# analogSignals.net
KiCad netlist of a schematic drawn in Altium Designer
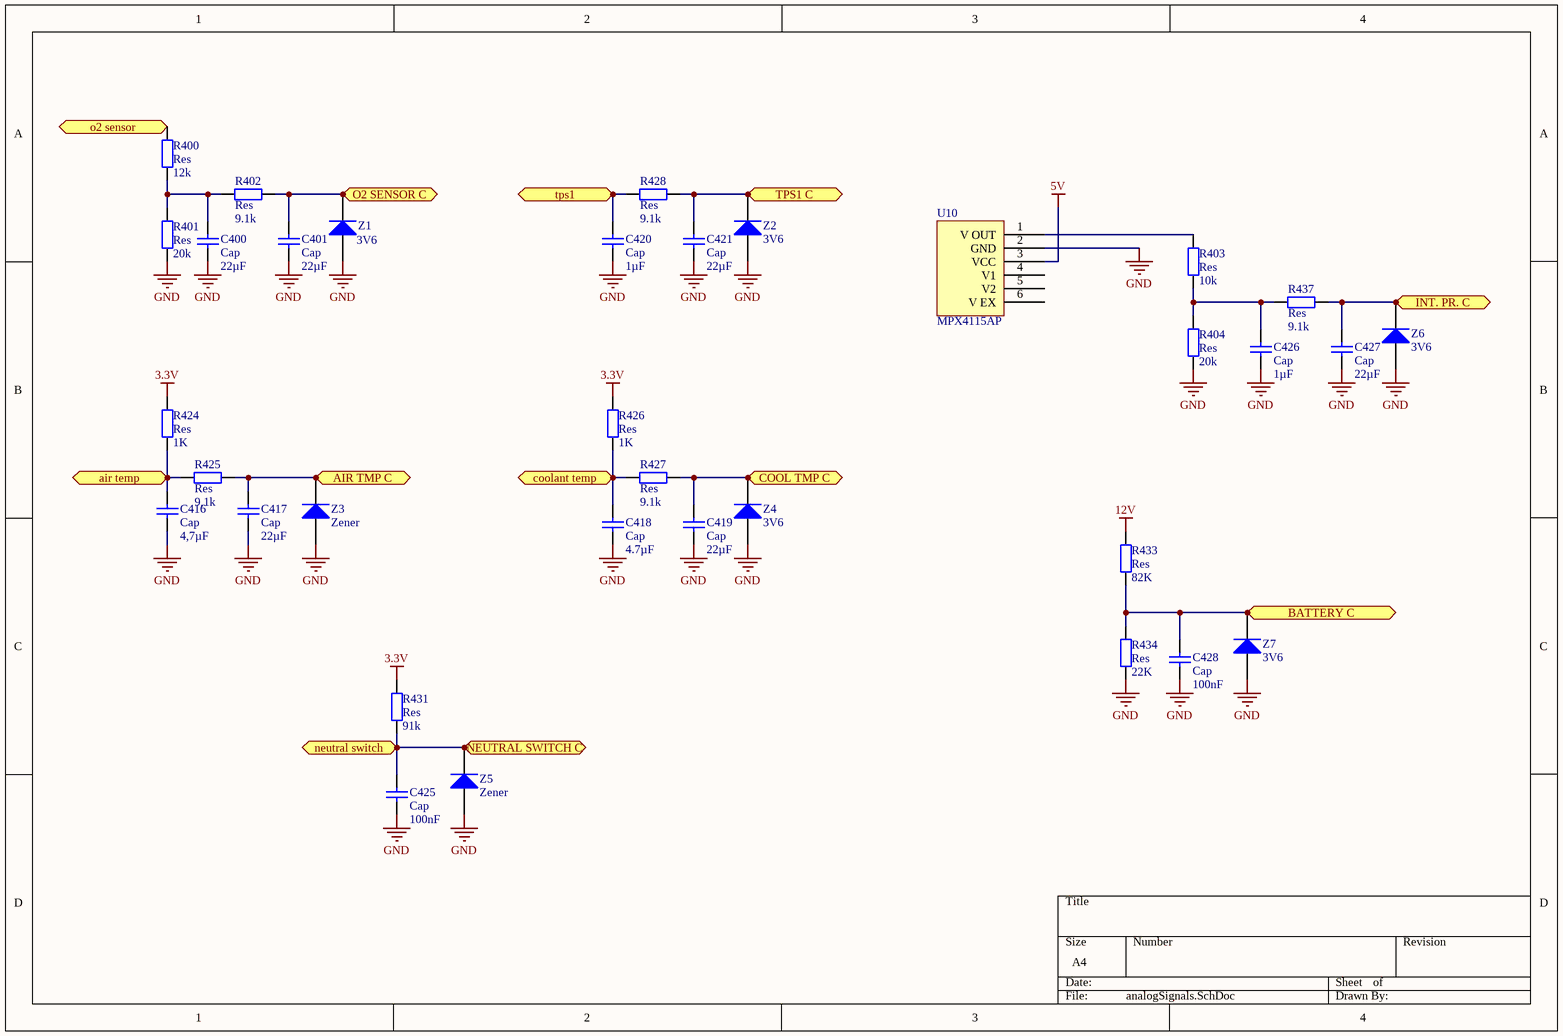
[diagram p0: analogSignals.SchDoc]

(export (version "E")
  (design (tool "Eeschema 10.0.6"))
  (components
    (comp (ref "C400")
      (value "Cap")
      (footprint "1206 footprint")
      (fields (field (name "ALTIUM_VALUE") "22µF"))
      (libsource (lib "ArduinoNano") (part "Cap"))
    )
    (comp (ref "C401")
      (value "Cap")
      (footprint "1206 footprint")
      (fields (field (name "ALTIUM_VALUE") "22µF"))
      (libsource (lib "ArduinoNano") (part "Cap"))
    )
    (comp (ref "C416")
      (value "Cap")
      (footprint "1206 footprint")
      (fields (field (name "ALTIUM_VALUE") "4,7µF"))
      (libsource (lib "ArduinoNano") (part "Cap"))
    )
    (comp (ref "C417")
      (value "Cap")
      (footprint "1206 footprint")
      (fields (field (name "ALTIUM_VALUE") "22µF"))
      (libsource (lib "ArduinoNano") (part "Cap"))
    )
    (comp (ref "C418")
      (value "Cap")
      (footprint "1206 footprint")
      (fields (field (name "ALTIUM_VALUE") "4.7µF"))
      (libsource (lib "ArduinoNano") (part "Cap"))
    )
    (comp (ref "C419")
      (value "Cap")
      (footprint "1206 footprint")
      (fields (field (name "ALTIUM_VALUE") "22µF"))
      (libsource (lib "ArduinoNano") (part "Cap"))
    )
    (comp (ref "C420")
      (value "Cap")
      (footprint "1206 footprint")
      (fields (field (name "ALTIUM_VALUE") "1µF"))
      (libsource (lib "ArduinoNano") (part "Cap"))
    )
    (comp (ref "C421")
      (value "Cap")
      (footprint "1206 footprint")
      (fields (field (name "ALTIUM_VALUE") "22µF"))
      (libsource (lib "ArduinoNano") (part "Cap"))
    )
    (comp (ref "C425")
      (value "Cap")
      (footprint "1206 footprint")
      (fields (field (name "ALTIUM_VALUE") "100nF"))
      (libsource (lib "ArduinoNano") (part "Cap"))
    )
    (comp (ref "C426")
      (value "Cap")
      (footprint "1206 footprint")
      (fields (field (name "ALTIUM_VALUE") "1µF"))
      (libsource (lib "ArduinoNano") (part "Cap"))
    )
    (comp (ref "C427")
      (value "Cap")
      (footprint "1206 footprint")
      (fields (field (name "ALTIUM_VALUE") "22µF"))
      (libsource (lib "ArduinoNano") (part "Cap"))
    )
    (comp (ref "C428")
      (value "Cap")
      (footprint "1206 footprint")
      (fields (field (name "ALTIUM_VALUE") "100nF"))
      (libsource (lib "ArduinoNano") (part "Cap"))
    )
    (comp (ref "R400")
      (value "Res")
      (footprint "1206 footprint")
      (fields (field (name "ALTIUM_VALUE") "12k"))
      (libsource (lib "ArduinoNano") (part "Res"))
    )
    (comp (ref "R401")
      (value "Res")
      (footprint "1206 footprint")
      (fields (field (name "ALTIUM_VALUE") "20k"))
      (libsource (lib "ArduinoNano") (part "Res"))
    )
    (comp (ref "R402")
      (value "Res")
      (footprint "1206 footprint")
      (fields (field (name "ALTIUM_VALUE") "9.1k"))
      (libsource (lib "") (part "Res_1"))
    )
    (comp (ref "R403")
      (value "Res")
      (footprint "1206 footprint")
      (fields (field (name "ALTIUM_VALUE") "10k"))
      (libsource (lib "ArduinoNano") (part "Res"))
    )
    (comp (ref "R404")
      (value "Res")
      (footprint "1206 footprint")
      (fields (field (name "ALTIUM_VALUE") "20k"))
      (libsource (lib "ArduinoNano") (part "Res"))
    )
    (comp (ref "R424")
      (value "Res")
      (footprint "1206 footprint")
      (fields (field (name "ALTIUM_VALUE") "1K"))
      (libsource (lib "ArduinoNano") (part "Res"))
    )
    (comp (ref "R425")
      (value "Res")
      (footprint "1206 footprint")
      (fields (field (name "ALTIUM_VALUE") "9,1k"))
      (libsource (lib "") (part "Res_1"))
    )
    (comp (ref "R426")
      (value "Res")
      (footprint "1206 footprint")
      (fields (field (name "ALTIUM_VALUE") "1K"))
      (libsource (lib "ArduinoNano") (part "Res"))
    )
    (comp (ref "R427")
      (value "Res")
      (footprint "1206 footprint")
      (fields (field (name "ALTIUM_VALUE") "9.1k"))
      (libsource (lib "") (part "Res_1"))
    )
    (comp (ref "R428")
      (value "Res")
      (footprint "1206 footprint")
      (fields (field (name "ALTIUM_VALUE") "9.1k"))
      (libsource (lib "") (part "Res_1"))
    )
    (comp (ref "R431")
      (value "Res")
      (footprint "1206 footprint")
      (fields (field (name "ALTIUM_VALUE") "91k"))
      (libsource (lib "ArduinoNano") (part "Res"))
    )
    (comp (ref "R433")
      (value "Res")
      (footprint "1206 footprint")
      (fields (field (name "ALTIUM_VALUE") "82K"))
      (libsource (lib "ArduinoNano") (part "Res"))
    )
    (comp (ref "R434")
      (value "Res")
      (footprint "1206 footprint")
      (fields (field (name "ALTIUM_VALUE") "22K"))
      (libsource (lib "ArduinoNano") (part "Res"))
    )
    (comp (ref "R437")
      (value "Res")
      (footprint "1206 footprint")
      (fields (field (name "ALTIUM_VALUE") "9.1k"))
      (libsource (lib "") (part "Res_1"))
    )
    (comp (ref "U10")
      (value "MPX4115AP")
      (footprint "MPX4115AP")
      (libsource (lib "ArduinoNano") (part "MPX4115AP"))
    )
    (comp (ref "Z1") (value "3V6") (footprint "SOD-80") (libsource (lib "ArduinoNano") (part "TZM")))
    (comp (ref "Z2") (value "3V6") (footprint "SOD-80") (libsource (lib "ArduinoNano") (part "TZM")))
    (comp (ref "Z3") (value "Zener") (footprint "SOD-80") (libsource (lib "ArduinoNano") (part "TZM")))
    (comp (ref "Z4") (value "3V6") (footprint "SOD-80") (libsource (lib "ArduinoNano") (part "TZM")))
    (comp (ref "Z5") (value "Zener") (footprint "SOD-80") (libsource (lib "ArduinoNano") (part "TZM")))
    (comp (ref "Z6") (value "3V6") (footprint "SOD-80") (libsource (lib "ArduinoNano") (part "TZM")))
    (comp (ref "Z7") (value "3V6") (footprint "SOD-80") (libsource (lib "ArduinoNano") (part "TZM")))
  )
  (nets
    (net (code "1") (name "/AIR TMP C") (class "Default")
      (node (ref "C417") (pin "2") (pinfunction "2_2") (pintype "passive"))
      (node (ref "R425") (pin "2") (pinfunction "2_2") (pintype "passive"))
      (node (ref "Z3") (pin "2") (pinfunction "K_2") (pintype "passive"))
    )
    (net (code "2") (name "/BATTERY C") (class "Default")
      (node (ref "C428") (pin "2") (pinfunction "2_2") (pintype "passive"))
      (node (ref "R433") (pin "1") (pinfunction "1_1") (pintype "passive"))
      (node (ref "R434") (pin "2") (pinfunction "2_2") (pintype "passive"))
      (node (ref "Z7") (pin "2") (pinfunction "K_2") (pintype "passive"))
    )
    (net (code "3") (name "/COOL TMP C") (class "Default")
      (node (ref "C419") (pin "2") (pinfunction "2_2") (pintype "passive"))
      (node (ref "R427") (pin "2") (pinfunction "2_2") (pintype "passive"))
      (node (ref "Z4") (pin "2") (pinfunction "K_2") (pintype "passive"))
    )
    (net (code "4") (name "/INT. PR. C") (class "Default")
      (node (ref "C427") (pin "2") (pinfunction "2_2") (pintype "passive"))
      (node (ref "R437") (pin "2") (pinfunction "2_2") (pintype "passive"))
      (node (ref "Z6") (pin "2") (pinfunction "K_2") (pintype "passive"))
    )
    (net (code "5") (name "/NEUTRAL SWITCH C") (class "Default")
      (node (ref "C425") (pin "2") (pinfunction "2_2") (pintype "passive"))
      (node (ref "R431") (pin "1") (pinfunction "1_1") (pintype "passive"))
      (node (ref "Z5") (pin "2") (pinfunction "K_2") (pintype "passive"))
    )
    (net (code "6") (name "/O2 SENSOR C") (class "Default")
      (node (ref "C401") (pin "2") (pinfunction "2_2") (pintype "passive"))
      (node (ref "R402") (pin "2") (pinfunction "2_2") (pintype "passive"))
      (node (ref "Z1") (pin "2") (pinfunction "K_2") (pintype "passive"))
    )
    (net (code "7") (name "/TPS1 C") (class "Default")
      (node (ref "C421") (pin "2") (pinfunction "2_2") (pintype "passive"))
      (node (ref "R428") (pin "2") (pinfunction "2_2") (pintype "passive"))
      (node (ref "Z2") (pin "2") (pinfunction "K_2") (pintype "passive"))
    )
    (net (code "8") (name "/air temp") (class "Default")
      (node (ref "C416") (pin "2") (pinfunction "2_2") (pintype "passive"))
      (node (ref "R424") (pin "1") (pinfunction "1_1") (pintype "passive"))
      (node (ref "R425") (pin "1") (pinfunction "1_1") (pintype "passive"))
    )
    (net (code "9") (name "/coolant temp") (class "Default")
      (node (ref "C418") (pin "2") (pinfunction "2_2") (pintype "passive"))
      (node (ref "R426") (pin "1") (pinfunction "1_1") (pintype "passive"))
      (node (ref "R427") (pin "1") (pinfunction "1_1") (pintype "passive"))
    )
    (net (code "10") (name "/o2 sensor") (class "Default")
      (node (ref "R400") (pin "2") (pinfunction "2_2") (pintype "passive"))
    )
    (net (code "11") (name "/tps1") (class "Default")
      (node (ref "C420") (pin "2") (pinfunction "2_2") (pintype "passive"))
      (node (ref "R428") (pin "1") (pinfunction "1_1") (pintype "passive"))
    )
    (net (code "12") (name "3.3V") (class "Default")
      (node (ref "R424") (pin "2") (pinfunction "2_2") (pintype "passive"))
      (node (ref "R426") (pin "2") (pinfunction "2_2") (pintype "passive"))
      (node (ref "R431") (pin "2") (pinfunction "2_2") (pintype "passive"))
    )
    (net (code "13") (name "5V") (class "Default")
      (node (ref "U10") (pin "3") (pinfunction "VCC_3") (pintype "passive"))
    )
    (net (code "14") (name "12V") (class "Default")
      (node (ref "R433") (pin "2") (pinfunction "2_2") (pintype "passive"))
    )
    (net (code "15") (name "GND") (class "Default")
      (node (ref "C400") (pin "1") (pinfunction "1_1") (pintype "passive"))
      (node (ref "C401") (pin "1") (pinfunction "1_1") (pintype "passive"))
      (node (ref "C416") (pin "1") (pinfunction "1_1") (pintype "passive"))
      (node (ref "C417") (pin "1") (pinfunction "1_1") (pintype "passive"))
      (node (ref "C418") (pin "1") (pinfunction "1_1") (pintype "passive"))
      (node (ref "C419") (pin "1") (pinfunction "1_1") (pintype "passive"))
      (node (ref "C420") (pin "1") (pinfunction "1_1") (pintype "passive"))
      (node (ref "C421") (pin "1") (pinfunction "1_1") (pintype "passive"))
      (node (ref "C425") (pin "1") (pinfunction "1_1") (pintype "passive"))
      (node (ref "C426") (pin "1") (pinfunction "1_1") (pintype "passive"))
      (node (ref "C427") (pin "1") (pinfunction "1_1") (pintype "passive"))
      (node (ref "C428") (pin "1") (pinfunction "1_1") (pintype "passive"))
      (node (ref "R401") (pin "1") (pinfunction "1_1") (pintype "passive"))
      (node (ref "R404") (pin "1") (pinfunction "1_1") (pintype "passive"))
      (node (ref "R434") (pin "1") (pinfunction "1_1") (pintype "passive"))
      (node (ref "U10") (pin "2") (pinfunction "GND_2") (pintype "passive"))
      (node (ref "Z1") (pin "1") (pinfunction "A_1") (pintype "passive"))
      (node (ref "Z2") (pin "1") (pinfunction "A_1") (pintype "passive"))
      (node (ref "Z3") (pin "1") (pinfunction "A_1") (pintype "passive"))
      (node (ref "Z4") (pin "1") (pinfunction "A_1") (pintype "passive"))
      (node (ref "Z5") (pin "1") (pinfunction "A_1") (pintype "passive"))
      (node (ref "Z6") (pin "1") (pinfunction "A_1") (pintype "passive"))
      (node (ref "Z7") (pin "1") (pinfunction "A_1") (pintype "passive"))
    )
    (net (code "16") (name "Net-(C400-Pad2)") (class "Default")
      (node (ref "C400") (pin "2") (pinfunction "2_2") (pintype "passive"))
      (node (ref "R400") (pin "1") (pinfunction "1_1") (pintype "passive"))
      (node (ref "R401") (pin "2") (pinfunction "2_2") (pintype "passive"))
      (node (ref "R402") (pin "1") (pinfunction "1_1") (pintype "passive"))
    )
    (net (code "17") (name "Net-(C426-Pad2)") (class "Default")
      (node (ref "C426") (pin "2") (pinfunction "2_2") (pintype "passive"))
      (node (ref "R403") (pin "1") (pinfunction "1_1") (pintype "passive"))
      (node (ref "R404") (pin "2") (pinfunction "2_2") (pintype "passive"))
      (node (ref "R437") (pin "1") (pinfunction "1_1") (pintype "passive"))
    )
    (net (code "18") (name "Net-(U10-V_OUT)") (class "Default")
      (node (ref "R403") (pin "2") (pinfunction "2_2") (pintype "passive"))
      (node (ref "U10") (pin "1") (pinfunction "V_OUT_1") (pintype "passive"))
    )
    (net (code "19") (name "unconnected-(U10-V1-Pad4)") (class "Default")
      (node (ref "U10") (pin "4") (pinfunction "V1_4") (pintype "passive"))
    )
    (net (code "20") (name "unconnected-(U10-V2-Pad5)") (class "Default")
      (node (ref "U10") (pin "5") (pinfunction "V2_5") (pintype "passive"))
    )
    (net (code "21") (name "unconnected-(U10-V_EX-Pad6)") (class "Default")
      (node (ref "U10") (pin "6") (pinfunction "V_EX_6") (pintype "passive"))
    )
  )
)
